# Dash22_ENCOD.net
KiCad netlist of a schematic drawn in Altium Designer
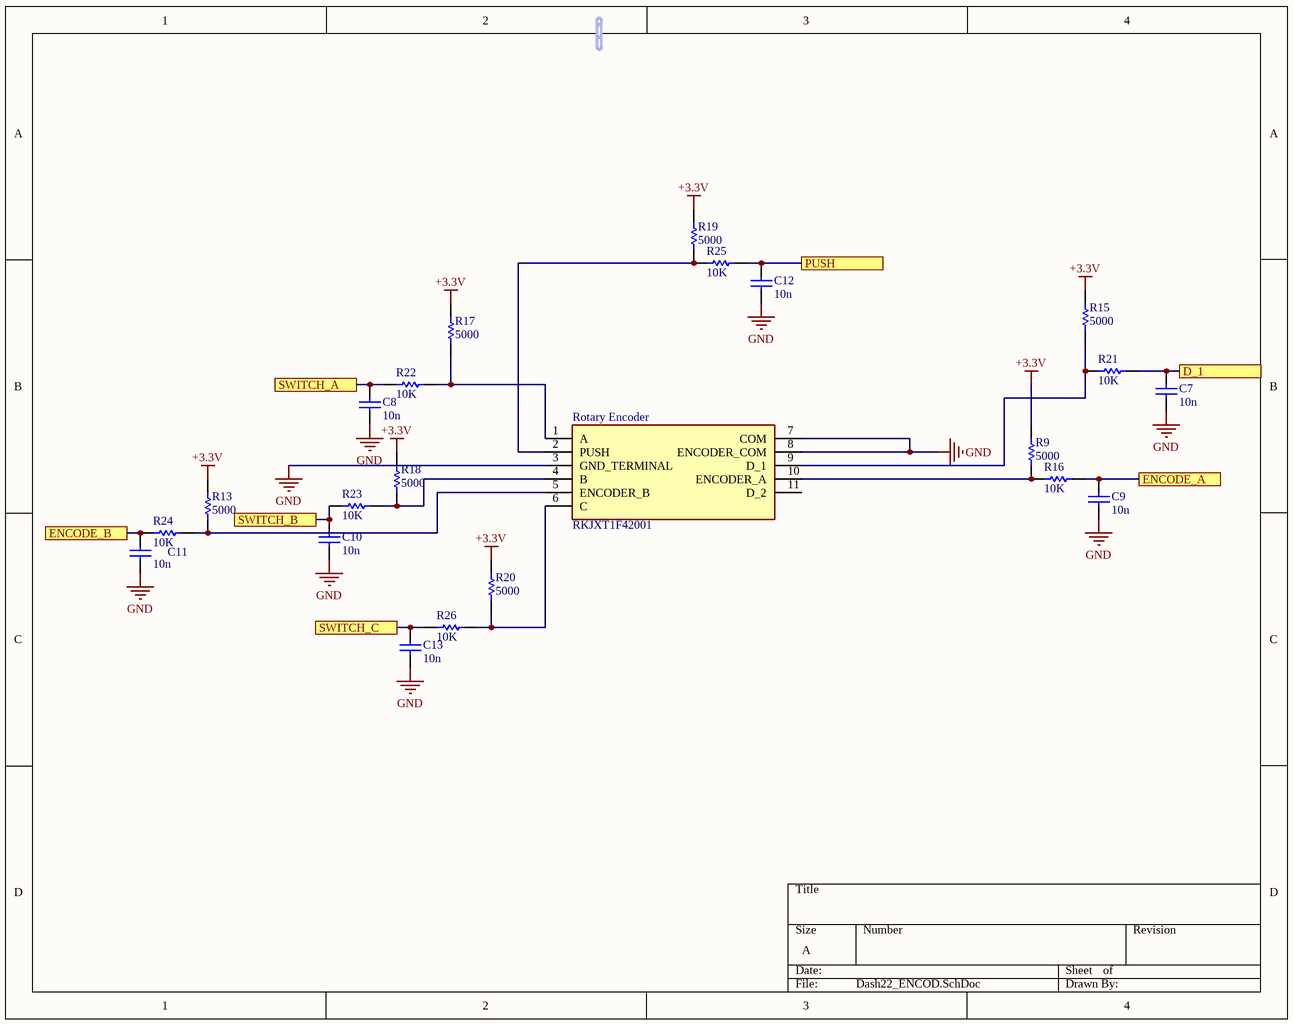
[diagram p0: Dash22_ENCOD.SchDoc]

(export (version "E")
  (design (tool "Eeschema 10.0.6"))
  (components
    (comp (ref "C7")
      (value "10n")
      (footprint "CAPC1608X90X35ML10T15")
      (description "Chip Capacitor, 10 nF, +/- 10%, 50 V, -55 to 125 degC, 0603 (1608 Metric), RoHS, Tape and Reel")
      (fields (field (name "VOLTAGE") "50V") (field (name "TOLERANCE") "10%"))
      (libsource (lib "Altium Content Vault") (part "CAP-NP-2"))
    )
    (comp (ref "C8")
      (value "10n")
      (footprint "CAPC1608X90X35ML10T15")
      (description "Chip Capacitor, 10 nF, +/- 10%, 50 V, -55 to 125 degC, 0603 (1608 Metric), RoHS, Tape and Reel")
      (fields (field (name "VOLTAGE") "50V") (field (name "TOLERANCE") "10%"))
      (libsource (lib "Altium Content Vault") (part "CAP-NP-2"))
    )
    (comp (ref "C9")
      (value "10n")
      (footprint "CAPC1608X90X35ML10T15")
      (description "Chip Capacitor, 10 nF, +/- 10%, 50 V, -55 to 125 degC, 0603 (1608 Metric), RoHS, Tape and Reel")
      (fields (field (name "VOLTAGE") "50V") (field (name "TOLERANCE") "10%"))
      (libsource (lib "Altium Content Vault") (part "CAP-NP-2"))
    )
    (comp (ref "C10")
      (value "10n")
      (footprint "CAPC1608X90X35ML10T15")
      (description "Chip Capacitor, 10 nF, +/- 10%, 50 V, -55 to 125 degC, 0603 (1608 Metric), RoHS, Tape and Reel")
      (fields (field (name "VOLTAGE") "50V") (field (name "TOLERANCE") "10%"))
      (libsource (lib "Altium Content Vault") (part "CAP-NP-2"))
    )
    (comp (ref "C11")
      (value "10n")
      (footprint "CAPC1608X90X35ML10T15")
      (description "Chip Capacitor, 10 nF, +/- 10%, 50 V, -55 to 125 degC, 0603 (1608 Metric), RoHS, Tape and Reel")
      (fields (field (name "VOLTAGE") "50V") (field (name "TOLERANCE") "10%"))
      (libsource (lib "Altium Content Vault") (part "CAP-NP-2"))
    )
    (comp (ref "C12")
      (value "10n")
      (footprint "CAPC1608X90X35ML10T15")
      (description "Chip Capacitor, 10 nF, +/- 10%, 50 V, -55 to 125 degC, 0603 (1608 Metric), RoHS, Tape and Reel")
      (fields (field (name "VOLTAGE") "50V") (field (name "TOLERANCE") "10%"))
      (libsource (lib "Altium Content Vault") (part "CAP-NP-2"))
    )
    (comp (ref "C13")
      (value "10n")
      (footprint "CAPC1608X90X35ML10T15")
      (description "Chip Capacitor, 10 nF, +/- 10%, 50 V, -55 to 125 degC, 0603 (1608 Metric), RoHS, Tape and Reel")
      (fields (field (name "VOLTAGE") "50V") (field (name "TOLERANCE") "10%"))
      (libsource (lib "Altium Content Vault") (part "CAP-NP-2"))
    )
    (comp (ref "R9")
      (value "5000")
      (footprint "RESC1608X55X25ML10T15")
      (description "Chip Resistor, 0 Ohm, 0.1 W, -55 to 155 degC, 0603 (1608 Metric)")
      (libsource (lib "Illini Formula Electric") (part "Symbol"))
    )
    (comp (ref "R13")
      (value "5000")
      (footprint "RESC1608X55X25ML10T15")
      (description "Chip Resistor, 0 Ohm, 0.1 W, -55 to 155 degC, 0603 (1608 Metric)")
      (libsource (lib "Illini Formula Electric") (part "Symbol"))
    )
    (comp (ref "R15")
      (value "5000")
      (footprint "RESC1608X55X25ML10T15")
      (description "Chip Resistor, 0 Ohm, 0.1 W, -55 to 155 degC, 0603 (1608 Metric)")
      (libsource (lib "Illini Formula Electric") (part "Symbol"))
    )
    (comp (ref "R16")
      (value "10K")
      (footprint "RESC1608X55X25ML10T15")
      (description "Chip Resistor, 0 Ohm, 0.1 W, -55 to 155 degC, 0603 (1608 Metric)")
      (libsource (lib "Illini Formula Electric") (part "Symbol"))
    )
    (comp (ref "R17")
      (value "5000")
      (footprint "RESC1608X55X25ML10T15")
      (description "Chip Resistor, 0 Ohm, 0.1 W, -55 to 155 degC, 0603 (1608 Metric)")
      (libsource (lib "Illini Formula Electric") (part "Symbol"))
    )
    (comp (ref "R18")
      (value "5000")
      (footprint "RESC1608X55X25ML10T15")
      (description "Chip Resistor, 0 Ohm, 0.1 W, -55 to 155 degC, 0603 (1608 Metric)")
      (libsource (lib "Illini Formula Electric") (part "Symbol"))
    )
    (comp (ref "R19")
      (value "5000")
      (footprint "RESC1608X55X25ML10T15")
      (description "Chip Resistor, 0 Ohm, 0.1 W, -55 to 155 degC, 0603 (1608 Metric)")
      (libsource (lib "Illini Formula Electric") (part "Symbol"))
    )
    (comp (ref "R20")
      (value "5000")
      (footprint "RESC1608X55X25ML10T15")
      (description "Chip Resistor, 0 Ohm, 0.1 W, -55 to 155 degC, 0603 (1608 Metric)")
      (libsource (lib "Illini Formula Electric") (part "Symbol"))
    )
    (comp (ref "R21")
      (value "10K")
      (footprint "RESC1608X55X25ML10T15")
      (description "Chip Resistor, 0 Ohm, 0.1 W, -55 to 155 degC, 0603 (1608 Metric)")
      (libsource (lib "Illini Formula Electric") (part "Symbol"))
    )
    (comp (ref "R22")
      (value "10K")
      (footprint "RESC1608X55X25ML10T15")
      (description "Chip Resistor, 0 Ohm, 0.1 W, -55 to 155 degC, 0603 (1608 Metric)")
      (libsource (lib "Illini Formula Electric") (part "Symbol"))
    )
    (comp (ref "R23")
      (value "10K")
      (footprint "RESC1608X55X25ML10T15")
      (description "Chip Resistor, 0 Ohm, 0.1 W, -55 to 155 degC, 0603 (1608 Metric)")
      (libsource (lib "Illini Formula Electric") (part "Symbol"))
    )
    (comp (ref "R24")
      (value "10K")
      (footprint "RESC1608X55X25ML10T15")
      (description "Chip Resistor, 0 Ohm, 0.1 W, -55 to 155 degC, 0603 (1608 Metric)")
      (libsource (lib "Illini Formula Electric") (part "Symbol"))
    )
    (comp (ref "R25")
      (value "10K")
      (footprint "RESC1608X55X25ML10T15")
      (description "Chip Resistor, 0 Ohm, 0.1 W, -55 to 155 degC, 0603 (1608 Metric)")
      (libsource (lib "Illini Formula Electric") (part "Symbol"))
    )
    (comp (ref "R26")
      (value "10K")
      (footprint "RESC1608X55X25ML10T15")
      (description "Chip Resistor, 0 Ohm, 0.1 W, -55 to 155 degC, 0603 (1608 Metric)")
      (libsource (lib "Illini Formula Electric") (part "Symbol"))
    )
    (comp (ref "Rotary Encoder")
      (value "RKJXT1F42001")
      (footprint "SamacSys:RKJXT1F42001")
      (description "Switch")
      (fields (field (name "MOUSER PART NUMBER") "688-RKJXT1F42001"))
      (libsource (lib "*") (part "RKJXT1F42001"))
    )
  )
  (nets
    (net (code "1") (name "+3.3V") (class "Default")
      (node (ref "R13") (pin "2") (pinfunction "2_2") (pintype "passive"))
      (node (ref "R15") (pin "2") (pinfunction "2_2") (pintype "passive"))
      (node (ref "R17") (pin "2") (pinfunction "2_2") (pintype "passive"))
      (node (ref "R18") (pin "2") (pinfunction "2_2") (pintype "passive"))
      (node (ref "R19") (pin "2") (pinfunction "2_2") (pintype "passive"))
      (node (ref "R20") (pin "2") (pinfunction "2_2") (pintype "passive"))
      (node (ref "R9") (pin "2") (pinfunction "2_2") (pintype "passive"))
    )
    (net (code "2") (name "/D_1") (class "Default")
      (node (ref "C7") (pin "2") (pinfunction "2_2") (pintype "passive"))
      (node (ref "R21") (pin "2") (pinfunction "2_2") (pintype "passive"))
    )
    (net (code "3") (name "/ENCODE_A") (class "Default")
      (node (ref "C9") (pin "2") (pinfunction "2_2") (pintype "passive"))
      (node (ref "R16") (pin "2") (pinfunction "2_2") (pintype "passive"))
    )
    (net (code "4") (name "/ENCODE_B") (class "Default")
      (node (ref "C11") (pin "2") (pinfunction "2_2") (pintype "passive"))
      (node (ref "R24") (pin "1") (pinfunction "1_1") (pintype "passive"))
    )
    (net (code "5") (name "/PUSH") (class "Default")
      (node (ref "C12") (pin "2") (pinfunction "2_2") (pintype "passive"))
      (node (ref "R25") (pin "2") (pinfunction "2_2") (pintype "passive"))
    )
    (net (code "6") (name "/SWITCH_A") (class "Default")
      (node (ref "C8") (pin "2") (pinfunction "2_2") (pintype "passive"))
      (node (ref "R22") (pin "1") (pinfunction "1_1") (pintype "passive"))
    )
    (net (code "7") (name "/SWITCH_B") (class "Default")
      (node (ref "C10") (pin "2") (pinfunction "2_2") (pintype "passive"))
      (node (ref "R23") (pin "1") (pinfunction "1_1") (pintype "passive"))
    )
    (net (code "8") (name "/SWITCH_C") (class "Default")
      (node (ref "C13") (pin "2") (pinfunction "2_2") (pintype "passive"))
      (node (ref "R26") (pin "1") (pinfunction "1_1") (pintype "passive"))
    )
    (net (code "9") (name "GND") (class "Default")
      (node (ref "C10") (pin "1") (pinfunction "1_1") (pintype "passive"))
      (node (ref "C11") (pin "1") (pinfunction "1_1") (pintype "passive"))
      (node (ref "C12") (pin "1") (pinfunction "1_1") (pintype "passive"))
      (node (ref "C13") (pin "1") (pinfunction "1_1") (pintype "passive"))
      (node (ref "C7") (pin "1") (pinfunction "1_1") (pintype "passive"))
      (node (ref "C8") (pin "1") (pinfunction "1_1") (pintype "passive"))
      (node (ref "C9") (pin "1") (pinfunction "1_1") (pintype "passive"))
      (node (ref "Rotary Encoder") (pin "3") (pinfunction "GND_TERMINAL_3") (pintype "passive"))
      (node (ref "Rotary Encoder") (pin "7") (pinfunction "COM_7") (pintype "passive"))
      (node (ref "Rotary Encoder") (pin "8") (pinfunction "ENCODER_COM_8") (pintype "passive"))
    )
    (net (code "10") (name "Net-(Rotary Encoder-A)") (class "Default")
      (node (ref "R17") (pin "1") (pinfunction "1_1") (pintype "passive"))
      (node (ref "R22") (pin "2") (pinfunction "2_2") (pintype "passive"))
      (node (ref "Rotary Encoder") (pin "1") (pinfunction "A_1") (pintype "passive"))
    )
    (net (code "11") (name "Net-(Rotary Encoder-B)") (class "Default")
      (node (ref "R18") (pin "1") (pinfunction "1_1") (pintype "passive"))
      (node (ref "R23") (pin "2") (pinfunction "2_2") (pintype "passive"))
      (node (ref "Rotary Encoder") (pin "4") (pinfunction "B_4") (pintype "passive"))
    )
    (net (code "12") (name "Net-(Rotary Encoder-C)") (class "Default")
      (node (ref "R20") (pin "1") (pinfunction "1_1") (pintype "passive"))
      (node (ref "R26") (pin "2") (pinfunction "2_2") (pintype "passive"))
      (node (ref "Rotary Encoder") (pin "6") (pinfunction "C_6") (pintype "passive"))
    )
    (net (code "13") (name "Net-(Rotary Encoder-D_1)") (class "Default")
      (node (ref "R15") (pin "1") (pinfunction "1_1") (pintype "passive"))
      (node (ref "R21") (pin "1") (pinfunction "1_1") (pintype "passive"))
      (node (ref "Rotary Encoder") (pin "9") (pinfunction "D_1_9") (pintype "passive"))
    )
    (net (code "14") (name "Net-(Rotary Encoder-ENCODER_A)") (class "Default")
      (node (ref "R16") (pin "1") (pinfunction "1_1") (pintype "passive"))
      (node (ref "R9") (pin "1") (pinfunction "1_1") (pintype "passive"))
      (node (ref "Rotary Encoder") (pin "10") (pinfunction "ENCODER_A_10") (pintype "passive"))
    )
    (net (code "15") (name "Net-(Rotary Encoder-ENCODER_B)") (class "Default")
      (node (ref "R13") (pin "1") (pinfunction "1_1") (pintype "passive"))
      (node (ref "R24") (pin "2") (pinfunction "2_2") (pintype "passive"))
      (node (ref "Rotary Encoder") (pin "5") (pinfunction "ENCODER_B_5") (pintype "passive"))
    )
    (net (code "16") (name "Net-(Rotary Encoder-PUSH)") (class "Default")
      (node (ref "R19") (pin "1") (pinfunction "1_1") (pintype "passive"))
      (node (ref "R25") (pin "1") (pinfunction "1_1") (pintype "passive"))
      (node (ref "Rotary Encoder") (pin "2") (pinfunction "PUSH_2") (pintype "passive"))
    )
    (net (code "17") (name "unconnected-(Rotary Encoder-D_2-Pad11)") (class "Default")
      (node (ref "Rotary Encoder") (pin "11") (pinfunction "D_2_11") (pintype "passive"))
    )
  )
)
